# Analog_-_Low_Speed_SE.net
KiCad netlist of a schematic drawn in Altium Designer
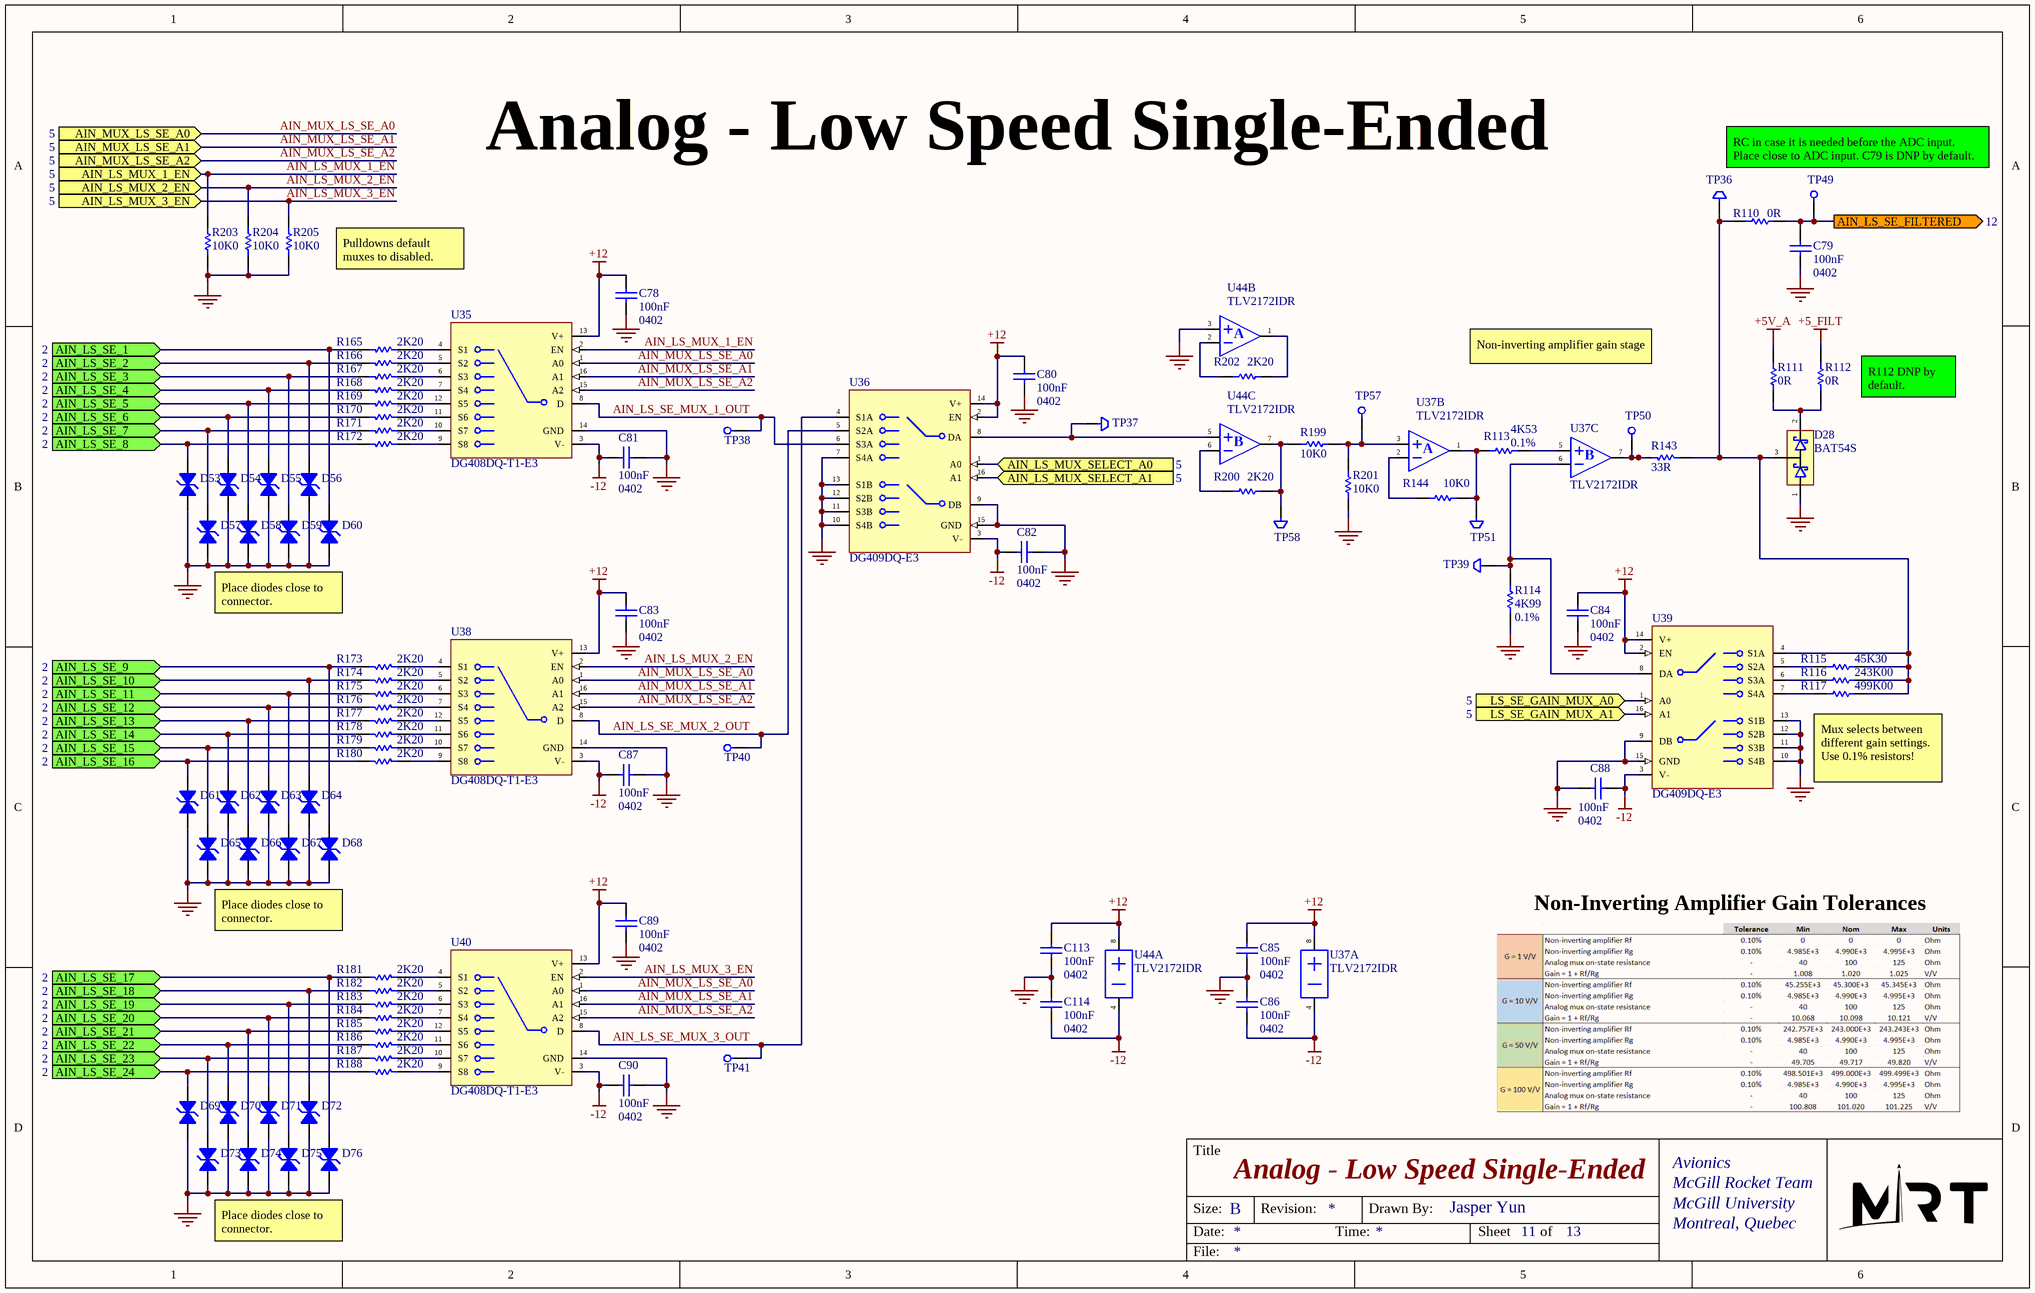
[diagram p0: Analog - Low Speed SE.SchDoc]

(export (version "E")
  (design (tool "Eeschema 10.0.6"))
  (components
    (comp (ref "C78")
      (value "100nF")
      (footprint "0402 CAP")
      (description "Capacitor")
      (fields (field (name "ALTIUM_VALUE") "0402") (field (name "PUBLISHER") "Altium Limited"))
      (libsource (lib "Miscellaneous Devices") (part "Cap"))
    )
    (comp (ref "C79")
      (value "100nF")
      (footprint "0402 CAP")
      (description "Capacitor")
      (fields (field (name "ALTIUM_VALUE") "0402") (field (name "PUBLISHER") "Altium Limited"))
      (libsource (lib "Miscellaneous Devices") (part "Cap"))
    )
    (comp (ref "C80")
      (value "100nF")
      (footprint "0402 CAP")
      (description "Capacitor")
      (fields (field (name "ALTIUM_VALUE") "0402") (field (name "PUBLISHER") "Altium Limited"))
      (libsource (lib "Miscellaneous Devices") (part "Cap"))
    )
    (comp (ref "C81")
      (value "100nF")
      (footprint "0402 CAP")
      (description "Capacitor")
      (fields (field (name "ALTIUM_VALUE") "0402") (field (name "PUBLISHER") "Altium Limited"))
      (libsource (lib "Miscellaneous Devices") (part "Cap"))
    )
    (comp (ref "C82")
      (value "100nF")
      (footprint "0402 CAP")
      (description "Capacitor")
      (fields (field (name "ALTIUM_VALUE") "0402") (field (name "PUBLISHER") "Altium Limited"))
      (libsource (lib "Miscellaneous Devices") (part "Cap"))
    )
    (comp (ref "C83")
      (value "100nF")
      (footprint "0402 CAP")
      (description "Capacitor")
      (fields (field (name "ALTIUM_VALUE") "0402") (field (name "PUBLISHER") "Altium Limited"))
      (libsource (lib "Miscellaneous Devices") (part "Cap"))
    )
    (comp (ref "C84")
      (value "100nF")
      (footprint "0402 CAP")
      (description "Capacitor")
      (fields (field (name "ALTIUM_VALUE") "0402") (field (name "PUBLISHER") "Altium Limited"))
      (libsource (lib "Miscellaneous Devices") (part "Cap"))
    )
    (comp (ref "C85")
      (value "100nF")
      (footprint "0402 CAP")
      (description "Capacitor")
      (fields (field (name "ALTIUM_VALUE") "0402") (field (name "PUBLISHER") "Altium Limited"))
      (libsource (lib "Miscellaneous Devices") (part "Cap"))
    )
    (comp (ref "C86")
      (value "100nF")
      (footprint "0402 CAP")
      (description "Capacitor")
      (fields (field (name "ALTIUM_VALUE") "0402") (field (name "PUBLISHER") "Altium Limited"))
      (libsource (lib "Miscellaneous Devices") (part "Cap"))
    )
    (comp (ref "C87")
      (value "100nF")
      (footprint "0402 CAP")
      (description "Capacitor")
      (fields (field (name "ALTIUM_VALUE") "0402") (field (name "PUBLISHER") "Altium Limited"))
      (libsource (lib "Miscellaneous Devices") (part "Cap"))
    )
    (comp (ref "C88")
      (value "100nF")
      (footprint "0402 CAP")
      (description "Capacitor")
      (fields (field (name "ALTIUM_VALUE") "0402") (field (name "PUBLISHER") "Altium Limited"))
      (libsource (lib "Miscellaneous Devices") (part "Cap"))
    )
    (comp (ref "C89")
      (value "100nF")
      (footprint "0402 CAP")
      (description "Capacitor")
      (fields (field (name "ALTIUM_VALUE") "0402") (field (name "PUBLISHER") "Altium Limited"))
      (libsource (lib "Miscellaneous Devices") (part "Cap"))
    )
    (comp (ref "C90")
      (value "100nF")
      (footprint "0402 CAP")
      (description "Capacitor")
      (fields (field (name "ALTIUM_VALUE") "0402") (field (name "PUBLISHER") "Altium Limited"))
      (libsource (lib "Miscellaneous Devices") (part "Cap"))
    )
    (comp (ref "C113")
      (value "100nF")
      (footprint "0402 CAP")
      (description "Capacitor")
      (fields (field (name "ALTIUM_VALUE") "0402") (field (name "PUBLISHER") "Altium Limited"))
      (libsource (lib "Miscellaneous Devices") (part "Cap"))
    )
    (comp (ref "C114")
      (value "100nF")
      (footprint "0402 CAP")
      (description "Capacitor")
      (fields (field (name "ALTIUM_VALUE") "0402") (field (name "PUBLISHER") "Altium Limited"))
      (libsource (lib "Miscellaneous Devices") (part "Cap"))
    )
    (comp (ref "D28")
      (value "BAT54S")
      (footprint "SOT23-3")
      (description "Rectifier Diode Small Signal Schottky 40V 0.3A 5ns 3-Pin SOT-23 T/R")
      (fields
        (field (name "MANUFACTURER") "STMicroelectronics")
        (field (name "MANUFACTURER PART NUMBER") "BAT54SFILM")
      )
      (libsource (lib "MRT SCH Library") (part "Schottky Diode Array BAT54S"))
    )
    (comp (ref "D53")
      (value "D12V0L1B2LP-7B")
      (footprint "DFN1006-2")
      (description "Bidirectional Zener diode")
      (libsource (lib "MRT SCH Library") (part "Diode Zener Bidirectional"))
    )
    (comp (ref "D54")
      (value "D12V0L1B2LP-7B")
      (footprint "DFN1006-2")
      (description "Bidirectional Zener diode")
      (libsource (lib "MRT SCH Library") (part "Diode Zener Bidirectional"))
    )
    (comp (ref "D55")
      (value "D12V0L1B2LP-7B")
      (footprint "DFN1006-2")
      (description "Bidirectional Zener diode")
      (libsource (lib "MRT SCH Library") (part "Diode Zener Bidirectional"))
    )
    (comp (ref "D56")
      (value "D12V0L1B2LP-7B")
      (footprint "DFN1006-2")
      (description "Bidirectional Zener diode")
      (libsource (lib "MRT SCH Library") (part "Diode Zener Bidirectional"))
    )
    (comp (ref "D57")
      (value "D12V0L1B2LP-7B")
      (footprint "DFN1006-2")
      (description "Bidirectional Zener diode")
      (libsource (lib "MRT SCH Library") (part "Diode Zener Bidirectional"))
    )
    (comp (ref "D58")
      (value "D12V0L1B2LP-7B")
      (footprint "DFN1006-2")
      (description "Bidirectional Zener diode")
      (libsource (lib "MRT SCH Library") (part "Diode Zener Bidirectional"))
    )
    (comp (ref "D59")
      (value "D12V0L1B2LP-7B")
      (footprint "DFN1006-2")
      (description "Bidirectional Zener diode")
      (libsource (lib "MRT SCH Library") (part "Diode Zener Bidirectional"))
    )
    (comp (ref "D60")
      (value "D12V0L1B2LP-7B")
      (footprint "DFN1006-2")
      (description "Bidirectional Zener diode")
      (libsource (lib "MRT SCH Library") (part "Diode Zener Bidirectional"))
    )
    (comp (ref "D61")
      (value "D12V0L1B2LP-7B")
      (footprint "DFN1006-2")
      (description "Bidirectional Zener diode")
      (libsource (lib "MRT SCH Library") (part "Diode Zener Bidirectional"))
    )
    (comp (ref "D62")
      (value "D12V0L1B2LP-7B")
      (footprint "DFN1006-2")
      (description "Bidirectional Zener diode")
      (libsource (lib "MRT SCH Library") (part "Diode Zener Bidirectional"))
    )
    (comp (ref "D63")
      (value "D12V0L1B2LP-7B")
      (footprint "DFN1006-2")
      (description "Bidirectional Zener diode")
      (libsource (lib "MRT SCH Library") (part "Diode Zener Bidirectional"))
    )
    (comp (ref "D64")
      (value "D12V0L1B2LP-7B")
      (footprint "DFN1006-2")
      (description "Bidirectional Zener diode")
      (libsource (lib "MRT SCH Library") (part "Diode Zener Bidirectional"))
    )
    (comp (ref "D65")
      (value "D12V0L1B2LP-7B")
      (footprint "DFN1006-2")
      (description "Bidirectional Zener diode")
      (libsource (lib "MRT SCH Library") (part "Diode Zener Bidirectional"))
    )
    (comp (ref "D66")
      (value "D12V0L1B2LP-7B")
      (footprint "DFN1006-2")
      (description "Bidirectional Zener diode")
      (libsource (lib "MRT SCH Library") (part "Diode Zener Bidirectional"))
    )
    (comp (ref "D67")
      (value "D12V0L1B2LP-7B")
      (footprint "DFN1006-2")
      (description "Bidirectional Zener diode")
      (libsource (lib "MRT SCH Library") (part "Diode Zener Bidirectional"))
    )
    (comp (ref "D68")
      (value "D12V0L1B2LP-7B")
      (footprint "DFN1006-2")
      (description "Bidirectional Zener diode")
      (libsource (lib "MRT SCH Library") (part "Diode Zener Bidirectional"))
    )
    (comp (ref "D69")
      (value "D12V0L1B2LP-7B")
      (footprint "DFN1006-2")
      (description "Bidirectional Zener diode")
      (libsource (lib "MRT SCH Library") (part "Diode Zener Bidirectional"))
    )
    (comp (ref "D70")
      (value "D12V0L1B2LP-7B")
      (footprint "DFN1006-2")
      (description "Bidirectional Zener diode")
      (libsource (lib "MRT SCH Library") (part "Diode Zener Bidirectional"))
    )
    (comp (ref "D71")
      (value "D12V0L1B2LP-7B")
      (footprint "DFN1006-2")
      (description "Bidirectional Zener diode")
      (libsource (lib "MRT SCH Library") (part "Diode Zener Bidirectional"))
    )
    (comp (ref "D72")
      (value "D12V0L1B2LP-7B")
      (footprint "DFN1006-2")
      (description "Bidirectional Zener diode")
      (libsource (lib "MRT SCH Library") (part "Diode Zener Bidirectional"))
    )
    (comp (ref "D73")
      (value "D12V0L1B2LP-7B")
      (footprint "DFN1006-2")
      (description "Bidirectional Zener diode")
      (libsource (lib "MRT SCH Library") (part "Diode Zener Bidirectional"))
    )
    (comp (ref "D74")
      (value "D12V0L1B2LP-7B")
      (footprint "DFN1006-2")
      (description "Bidirectional Zener diode")
      (libsource (lib "MRT SCH Library") (part "Diode Zener Bidirectional"))
    )
    (comp (ref "D75")
      (value "D12V0L1B2LP-7B")
      (footprint "DFN1006-2")
      (description "Bidirectional Zener diode")
      (libsource (lib "MRT SCH Library") (part "Diode Zener Bidirectional"))
    )
    (comp (ref "D76")
      (value "D12V0L1B2LP-7B")
      (footprint "DFN1006-2")
      (description "Bidirectional Zener diode")
      (libsource (lib "MRT SCH Library") (part "Diode Zener Bidirectional"))
    )
    (comp (ref "R110")
      (value "0R")
      (footprint "0402 RES")
      (description "Resistor")
      (fields (field (name "PUBLISHER") "Altium Limited"))
      (libsource (lib "Miscellaneous Devices") (part "Res1"))
    )
    (comp (ref "R111")
      (value "0R")
      (footprint "0402 RES")
      (description "Resistor")
      (fields (field (name "PUBLISHER") "Altium Limited"))
      (libsource (lib "Miscellaneous Devices") (part "Res1"))
    )
    (comp (ref "R112")
      (value "0R")
      (footprint "0402 RES")
      (description "Resistor")
      (fields (field (name "PUBLISHER") "Altium Limited"))
      (libsource (lib "Miscellaneous Devices") (part "Res1"))
    )
    (comp (ref "R113")
      (value "4K53")
      (footprint "0402 RES")
      (description "Resistor")
      (fields (field (name "ALTIUM_VALUE") "0.1%") (field (name "PUBLISHER") "Altium Limited"))
      (libsource (lib "Miscellaneous Devices") (part "Res1"))
    )
    (comp (ref "R114")
      (value "4K99")
      (footprint "0402 RES")
      (description "Resistor")
      (fields (field (name "ALTIUM_VALUE") "0.1%") (field (name "PUBLISHER") "Altium Limited"))
      (libsource (lib "Miscellaneous Devices") (part "Res1"))
    )
    (comp (ref "R115")
      (value "45K30")
      (footprint "0402 RES")
      (description "Resistor")
      (fields (field (name "PUBLISHER") "Altium Limited"))
      (libsource (lib "Miscellaneous Devices") (part "Res1"))
    )
    (comp (ref "R116")
      (value "243K00")
      (footprint "0402 RES")
      (description "Resistor")
      (fields (field (name "PUBLISHER") "Altium Limited"))
      (libsource (lib "Miscellaneous Devices") (part "Res1"))
    )
    (comp (ref "R117")
      (value "499K00")
      (footprint "0402 RES")
      (description "Resistor")
      (fields (field (name "PUBLISHER") "Altium Limited"))
      (libsource (lib "Miscellaneous Devices") (part "Res1"))
    )
    (comp (ref "R143")
      (value "33R")
      (footprint "0402 RES")
      (description "Resistor")
      (fields (field (name "PUBLISHER") "Altium Limited"))
      (libsource (lib "Miscellaneous Devices") (part "Res1"))
    )
    (comp (ref "R144")
      (value "10K0")
      (footprint "0402 RES")
      (description "Resistor")
      (fields (field (name "PUBLISHER") "Altium Limited"))
      (libsource (lib "Miscellaneous Devices") (part "Res1"))
    )
    (comp (ref "R165")
      (value "2K20")
      (footprint "0402 RES")
      (description "Resistor")
      (fields (field (name "PUBLISHER") "Altium Limited"))
      (libsource (lib "Miscellaneous Devices") (part "Res1"))
    )
    (comp (ref "R166")
      (value "2K20")
      (footprint "0402 RES")
      (description "Resistor")
      (fields (field (name "PUBLISHER") "Altium Limited"))
      (libsource (lib "Miscellaneous Devices") (part "Res1"))
    )
    (comp (ref "R167")
      (value "2K20")
      (footprint "0402 RES")
      (description "Resistor")
      (fields (field (name "PUBLISHER") "Altium Limited"))
      (libsource (lib "Miscellaneous Devices") (part "Res1"))
    )
    (comp (ref "R168")
      (value "2K20")
      (footprint "0402 RES")
      (description "Resistor")
      (fields (field (name "PUBLISHER") "Altium Limited"))
      (libsource (lib "Miscellaneous Devices") (part "Res1"))
    )
    (comp (ref "R169")
      (value "2K20")
      (footprint "0402 RES")
      (description "Resistor")
      (fields (field (name "PUBLISHER") "Altium Limited"))
      (libsource (lib "Miscellaneous Devices") (part "Res1"))
    )
    (comp (ref "R170")
      (value "2K20")
      (footprint "0402 RES")
      (description "Resistor")
      (fields (field (name "PUBLISHER") "Altium Limited"))
      (libsource (lib "Miscellaneous Devices") (part "Res1"))
    )
    (comp (ref "R171")
      (value "2K20")
      (footprint "0402 RES")
      (description "Resistor")
      (fields (field (name "PUBLISHER") "Altium Limited"))
      (libsource (lib "Miscellaneous Devices") (part "Res1"))
    )
    (comp (ref "R172")
      (value "2K20")
      (footprint "0402 RES")
      (description "Resistor")
      (fields (field (name "PUBLISHER") "Altium Limited"))
      (libsource (lib "Miscellaneous Devices") (part "Res1"))
    )
    (comp (ref "R173")
      (value "2K20")
      (footprint "0402 RES")
      (description "Resistor")
      (fields (field (name "PUBLISHER") "Altium Limited"))
      (libsource (lib "Miscellaneous Devices") (part "Res1"))
    )
    (comp (ref "R174")
      (value "2K20")
      (footprint "0402 RES")
      (description "Resistor")
      (fields (field (name "PUBLISHER") "Altium Limited"))
      (libsource (lib "Miscellaneous Devices") (part "Res1"))
    )
    (comp (ref "R175")
      (value "2K20")
      (footprint "0402 RES")
      (description "Resistor")
      (fields (field (name "PUBLISHER") "Altium Limited"))
      (libsource (lib "Miscellaneous Devices") (part "Res1"))
    )
    (comp (ref "R176")
      (value "2K20")
      (footprint "0402 RES")
      (description "Resistor")
      (fields (field (name "PUBLISHER") "Altium Limited"))
      (libsource (lib "Miscellaneous Devices") (part "Res1"))
    )
    (comp (ref "R177")
      (value "2K20")
      (footprint "0402 RES")
      (description "Resistor")
      (fields (field (name "PUBLISHER") "Altium Limited"))
      (libsource (lib "Miscellaneous Devices") (part "Res1"))
    )
    (comp (ref "R178")
      (value "2K20")
      (footprint "0402 RES")
      (description "Resistor")
      (fields (field (name "PUBLISHER") "Altium Limited"))
      (libsource (lib "Miscellaneous Devices") (part "Res1"))
    )
    (comp (ref "R179")
      (value "2K20")
      (footprint "0402 RES")
      (description "Resistor")
      (fields (field (name "PUBLISHER") "Altium Limited"))
      (libsource (lib "Miscellaneous Devices") (part "Res1"))
    )
    (comp (ref "R180")
      (value "2K20")
      (footprint "0402 RES")
      (description "Resistor")
      (fields (field (name "PUBLISHER") "Altium Limited"))
      (libsource (lib "Miscellaneous Devices") (part "Res1"))
    )
    (comp (ref "R181")
      (value "2K20")
      (footprint "0402 RES")
      (description "Resistor")
      (fields (field (name "PUBLISHER") "Altium Limited"))
      (libsource (lib "Miscellaneous Devices") (part "Res1"))
    )
    (comp (ref "R182")
      (value "2K20")
      (footprint "0402 RES")
      (description "Resistor")
      (fields (field (name "PUBLISHER") "Altium Limited"))
      (libsource (lib "Miscellaneous Devices") (part "Res1"))
    )
    (comp (ref "R183")
      (value "2K20")
      (footprint "0402 RES")
      (description "Resistor")
      (fields (field (name "PUBLISHER") "Altium Limited"))
      (libsource (lib "Miscellaneous Devices") (part "Res1"))
    )
    (comp (ref "R184")
      (value "2K20")
      (footprint "0402 RES")
      (description "Resistor")
      (fields (field (name "PUBLISHER") "Altium Limited"))
      (libsource (lib "Miscellaneous Devices") (part "Res1"))
    )
    (comp (ref "R185")
      (value "2K20")
      (footprint "0402 RES")
      (description "Resistor")
      (fields (field (name "PUBLISHER") "Altium Limited"))
      (libsource (lib "Miscellaneous Devices") (part "Res1"))
    )
    (comp (ref "R186")
      (value "2K20")
      (footprint "0402 RES")
      (description "Resistor")
      (fields (field (name "PUBLISHER") "Altium Limited"))
      (libsource (lib "Miscellaneous Devices") (part "Res1"))
    )
    (comp (ref "R187")
      (value "2K20")
      (footprint "0402 RES")
      (description "Resistor")
      (fields (field (name "PUBLISHER") "Altium Limited"))
      (libsource (lib "Miscellaneous Devices") (part "Res1"))
    )
    (comp (ref "R188")
      (value "2K20")
      (footprint "0402 RES")
      (description "Resistor")
      (fields (field (name "PUBLISHER") "Altium Limited"))
      (libsource (lib "Miscellaneous Devices") (part "Res1"))
    )
    (comp (ref "R199")
      (value "10K0")
      (footprint "0402 RES")
      (description "Resistor")
      (fields (field (name "PUBLISHER") "Altium Limited"))
      (libsource (lib "Miscellaneous Devices") (part "Res1"))
    )
    (comp (ref "R200")
      (value "2K20")
      (footprint "0402 RES")
      (description "Resistor")
      (fields (field (name "PUBLISHER") "Altium Limited"))
      (libsource (lib "Miscellaneous Devices") (part "Res1"))
    )
    (comp (ref "R201")
      (value "10K0")
      (footprint "0402 RES")
      (description "Resistor")
      (fields (field (name "PUBLISHER") "Altium Limited"))
      (libsource (lib "Miscellaneous Devices") (part "Res1"))
    )
    (comp (ref "R202")
      (value "2K20")
      (footprint "0402 RES")
      (description "Resistor")
      (fields (field (name "PUBLISHER") "Altium Limited"))
      (libsource (lib "Miscellaneous Devices") (part "Res1"))
    )
    (comp (ref "R203")
      (value "10K0")
      (footprint "0402 RES")
      (description "Resistor")
      (fields (field (name "PUBLISHER") "Altium Limited"))
      (libsource (lib "Miscellaneous Devices") (part "Res1"))
    )
    (comp (ref "R204")
      (value "10K0")
      (footprint "0402 RES")
      (description "Resistor")
      (fields (field (name "PUBLISHER") "Altium Limited"))
      (libsource (lib "Miscellaneous Devices") (part "Res1"))
    )
    (comp (ref "R205")
      (value "10K0")
      (footprint "0402 RES")
      (description "Resistor")
      (fields (field (name "PUBLISHER") "Altium Limited"))
      (libsource (lib "Miscellaneous Devices") (part "Res1"))
    )
    (comp (ref "TP36")
      (value "Test Point - Keystone 5015")
      (footprint "Test Point Keystone 5015")
      (description "Keystone 5015 Test point")
      (libsource (lib "MRT SCH Library") (part "Test Point - Keystone 5015"))
    )
    (comp (ref "TP37")
      (value "Test Point - Keystone 5015")
      (footprint "Test Point Keystone 5015")
      (description "Keystone 5015 Test point")
      (libsource (lib "MRT SCH Library") (part "Test Point - Keystone 5015"))
    )
    (comp (ref "TP38")
      (value "Test Point - SMD Pad")
      (footprint "TEST POINT SMD PAD")
      (description "SMD Pad test point")
      (libsource (lib "MRT SCH Library") (part "Test Point - SMD Pad"))
    )
    (comp (ref "TP39")
      (value "Test Point - Keystone 5015")
      (footprint "Test Point Keystone 5015")
      (description "Keystone 5015 Test point")
      (libsource (lib "MRT SCH Library") (part "Test Point - Keystone 5015"))
    )
    (comp (ref "TP40")
      (value "Test Point - SMD Pad")
      (footprint "TEST POINT SMD PAD")
      (description "SMD Pad test point")
      (libsource (lib "MRT SCH Library") (part "Test Point - SMD Pad"))
    )
    (comp (ref "TP41")
      (value "Test Point - SMD Pad")
      (footprint "TEST POINT SMD PAD")
      (description "SMD Pad test point")
      (libsource (lib "MRT SCH Library") (part "Test Point - SMD Pad"))
    )
    (comp (ref "TP49")
      (value "Test Point - SMD Pad")
      (footprint "TEST POINT SMD PAD")
      (description "SMD Pad test point")
      (libsource (lib "MRT SCH Library") (part "Test Point - SMD Pad"))
    )
    (comp (ref "TP50")
      (value "Test Point - SMD Pad")
      (footprint "TEST POINT SMD PAD")
      (description "SMD Pad test point")
      (libsource (lib "MRT SCH Library") (part "Test Point - SMD Pad"))
    )
    (comp (ref "TP51")
      (value "Test Point - Keystone 5015")
      (footprint "Test Point Keystone 5015")
      (description "Keystone 5015 Test point")
      (libsource (lib "MRT SCH Library") (part "Test Point - Keystone 5015"))
    )
    (comp (ref "TP57")
      (value "Test Point - SMD Pad")
      (footprint "TEST POINT SMD PAD")
      (description "SMD Pad test point")
      (libsource (lib "MRT SCH Library") (part "Test Point - SMD Pad"))
    )
    (comp (ref "TP58")
      (value "Test Point - Keystone 5015")
      (footprint "Test Point Keystone 5015")
      (description "Keystone 5015 Test point")
      (libsource (lib "MRT SCH Library") (part "Test Point - Keystone 5015"))
    )
    (comp (ref "U35")
      (value "DG408DQ-T1-E3")
      (footprint "TSSOP-16")
      (description "DG408DQ-T1-E3; Multiplexer Single 8: 1; 15 V; 18 V; 24 V; 28 V; 16-Pin TSSOP")
      (fields (field (name "MANUFACTURER") "Vishay Siliconix"))
      (libsource (lib "MRT SCH Library") (part "Analog Mux DG408DQ-T1-E3"))
    )
    (comp (ref "U36")
      (value "DG409DQ-E3")
      (footprint "TSSOP-16")
      (description "DG409 Series 20 V 8-Ch/Dual 4-Ch High-Performance CMOS Analog Multiplexer")
      (fields (field (name "MANUFACTURER") "Vishay Siliconix"))
      (libsource (lib "") (part "Analog Mux DG409DQ-E3_1"))
    )
    (comp (ref "U37")
      (value "TLV2172IDR")
      (footprint "SOIC-8")
      (fields
        (field (name "MANUFACTURER") "Texas Instruments")
        (field (name "MANUFACTURER PART NUMBER") "RC4580IDR")
      )
      (libsource (lib "MRT SCH Library") (part "OP AMP RC4580"))
    )
    (comp (ref "U38")
      (value "DG408DQ-T1-E3")
      (footprint "TSSOP-16")
      (description "DG408DQ-T1-E3; Multiplexer Single 8: 1; 15 V; 18 V; 24 V; 28 V; 16-Pin TSSOP")
      (fields (field (name "MANUFACTURER") "Vishay Siliconix"))
      (libsource (lib "MRT SCH Library") (part "Analog Mux DG408DQ-T1-E3"))
    )
    (comp (ref "U39")
      (value "DG409DQ-E3")
      (footprint "TSSOP-16")
      (description "DG409 Series 20 V 8-Ch/Dual 4-Ch High-Performance CMOS Analog Multiplexer")
      (fields (field (name "MANUFACTURER") "Vishay Siliconix"))
      (libsource (lib "MRT SCH Library") (part "Analog Mux DG409DQ-E3"))
    )
    (comp (ref "U40")
      (value "DG408DQ-T1-E3")
      (footprint "TSSOP-16")
      (description "DG408DQ-T1-E3; Multiplexer Single 8: 1; 15 V; 18 V; 24 V; 28 V; 16-Pin TSSOP")
      (fields (field (name "MANUFACTURER") "Vishay Siliconix"))
      (libsource (lib "MRT SCH Library") (part "Analog Mux DG408DQ-T1-E3"))
    )
    (comp (ref "U44")
      (value "TLV2172IDR")
      (footprint "SOIC-8")
      (fields
        (field (name "MANUFACTURER") "Texas Instruments")
        (field (name "MANUFACTURER PART NUMBER") "RC4580IDR")
      )
      (libsource (lib "MRT SCH Library") (part "OP AMP RC4580"))
    )
  )
  (nets
    (net (code "1") (name "+5V_A") (class "Default")
      (node (ref "R111") (pin "1") (pinfunction "1_1") (pintype "passive"))
    )
    (net (code "2") (name "+5_FILT") (class "Default")
      (node (ref "R112") (pin "1") (pinfunction "1_1") (pintype "passive"))
    )
    (net (code "3") (name "+12") (class "Default")
      (node (ref "C113") (pin "2") (pinfunction "2_2") (pintype "passive"))
      (node (ref "C78") (pin "2") (pinfunction "2_2") (pintype "passive"))
      (node (ref "C80") (pin "2") (pinfunction "2_2") (pintype "passive"))
      (node (ref "C83") (pin "2") (pinfunction "2_2") (pintype "passive"))
      (node (ref "C84") (pin "2") (pinfunction "2_2") (pintype "passive"))
      (node (ref "C85") (pin "2") (pinfunction "2_2") (pintype "passive"))
      (node (ref "C89") (pin "2") (pinfunction "2_2") (pintype "passive"))
      (node (ref "U35") (pin "13") (pinfunction "V+_13") (pintype "passive"))
      (node (ref "U36") (pin "14") (pinfunction "V+_14") (pintype "passive"))
      (node (ref "U36") (pin "2") (pinfunction "EN_2") (pintype "input"))
      (node (ref "U37") (pin "8") (pinfunction "VCC+_8") (pintype "passive"))
      (node (ref "U38") (pin "13") (pinfunction "V+_13") (pintype "passive"))
      (node (ref "U39") (pin "14") (pinfunction "V+_14") (pintype "passive"))
      (node (ref "U39") (pin "2") (pinfunction "EN_2") (pintype "input"))
      (node (ref "U40") (pin "13") (pinfunction "V+_13") (pintype "passive"))
      (node (ref "U44") (pin "8") (pinfunction "VCC+_8") (pintype "passive"))
    )
    (net (code "4") (name "-12") (class "Default")
      (node (ref "C114") (pin "1") (pinfunction "1_1") (pintype "passive"))
      (node (ref "C81") (pin "2") (pinfunction "2_2") (pintype "passive"))
      (node (ref "C82") (pin "2") (pinfunction "2_2") (pintype "passive"))
      (node (ref "C86") (pin "1") (pinfunction "1_1") (pintype "passive"))
      (node (ref "C87") (pin "2") (pinfunction "2_2") (pintype "passive"))
      (node (ref "C88") (pin "2") (pinfunction "2_2") (pintype "passive"))
      (node (ref "C90") (pin "2") (pinfunction "2_2") (pintype "passive"))
      (node (ref "U35") (pin "3") (pinfunction "V-_3") (pintype "passive"))
      (node (ref "U36") (pin "3") (pinfunction "V-_3") (pintype "passive"))
      (node (ref "U37") (pin "4") (pinfunction "VCC-_4") (pintype "passive"))
      (node (ref "U38") (pin "3") (pinfunction "V-_3") (pintype "passive"))
      (node (ref "U39") (pin "3") (pinfunction "V-_3") (pintype "passive"))
      (node (ref "U40") (pin "3") (pinfunction "V-_3") (pintype "passive"))
      (node (ref "U44") (pin "4") (pinfunction "VCC-_4") (pintype "passive"))
    )
    (net (code "5") (name "/AIN_LS_MUX_1_EN") (class "Default")
      (node (ref "R203") (pin "1") (pinfunction "1_1") (pintype "passive"))
      (node (ref "U35") (pin "2") (pinfunction "EN_2") (pintype "input"))
    )
    (net (code "6") (name "/AIN_LS_MUX_2_EN") (class "Default")
      (node (ref "R204") (pin "1") (pinfunction "1_1") (pintype "passive"))
      (node (ref "U38") (pin "2") (pinfunction "EN_2") (pintype "input"))
    )
    (net (code "7") (name "/AIN_LS_MUX_3_EN") (class "Default")
      (node (ref "R205") (pin "1") (pinfunction "1_1") (pintype "passive"))
      (node (ref "U40") (pin "2") (pinfunction "EN_2") (pintype "input"))
    )
    (net (code "8") (name "/AIN_LS_MUX_SELECT_A0") (class "Default")
      (node (ref "U36") (pin "1") (pinfunction "A0_1") (pintype "input"))
    )
    (net (code "9") (name "/AIN_LS_MUX_SELECT_A1") (class "Default")
      (node (ref "U36") (pin "16") (pinfunction "A1_16") (pintype "input"))
    )
    (net (code "10") (name "/AIN_LS_SE_1") (class "Default")
      (node (ref "D60") (pin "2") (pinfunction "2_2") (pintype "passive"))
      (node (ref "R165") (pin "1") (pinfunction "1_1") (pintype "passive"))
    )
    (net (code "11") (name "/AIN_LS_SE_2") (class "Default")
      (node (ref "D56") (pin "2") (pinfunction "2_2") (pintype "passive"))
      (node (ref "R166") (pin "1") (pinfunction "1_1") (pintype "passive"))
    )
    (net (code "12") (name "/AIN_LS_SE_3") (class "Default")
      (node (ref "D59") (pin "2") (pinfunction "2_2") (pintype "passive"))
      (node (ref "R167") (pin "1") (pinfunction "1_1") (pintype "passive"))
    )
    (net (code "13") (name "/AIN_LS_SE_4") (class "Default")
      (node (ref "D55") (pin "2") (pinfunction "2_2") (pintype "passive"))
      (node (ref "R168") (pin "1") (pinfunction "1_1") (pintype "passive"))
    )
    (net (code "14") (name "/AIN_LS_SE_5") (class "Default")
      (node (ref "D58") (pin "2") (pinfunction "2_2") (pintype "passive"))
      (node (ref "R169") (pin "1") (pinfunction "1_1") (pintype "passive"))
    )
    (net (code "15") (name "/AIN_LS_SE_6") (class "Default")
      (node (ref "D54") (pin "2") (pinfunction "2_2") (pintype "passive"))
      (node (ref "R170") (pin "1") (pinfunction "1_1") (pintype "passive"))
    )
    (net (code "16") (name "/AIN_LS_SE_7") (class "Default")
      (node (ref "D57") (pin "2") (pinfunction "2_2") (pintype "passive"))
      (node (ref "R171") (pin "1") (pinfunction "1_1") (pintype "passive"))
    )
    (net (code "17") (name "/AIN_LS_SE_8") (class "Default")
      (node (ref "D53") (pin "2") (pinfunction "2_2") (pintype "passive"))
      (node (ref "R172") (pin "1") (pinfunction "1_1") (pintype "passive"))
    )
    (net (code "18") (name "/AIN_LS_SE_9") (class "Default")
      (node (ref "D68") (pin "2") (pinfunction "2_2") (pintype "passive"))
      (node (ref "R173") (pin "1") (pinfunction "1_1") (pintype "passive"))
    )
    (net (code "19") (name "/AIN_LS_SE_10") (class "Default")
      (node (ref "D64") (pin "2") (pinfunction "2_2") (pintype "passive"))
      (node (ref "R174") (pin "1") (pinfunction "1_1") (pintype "passive"))
    )
    (net (code "20") (name "/AIN_LS_SE_11") (class "Default")
      (node (ref "D67") (pin "2") (pinfunction "2_2") (pintype "passive"))
      (node (ref "R175") (pin "1") (pinfunction "1_1") (pintype "passive"))
    )
    (net (code "21") (name "/AIN_LS_SE_12") (class "Default")
      (node (ref "D63") (pin "2") (pinfunction "2_2") (pintype "passive"))
      (node (ref "R176") (pin "1") (pinfunction "1_1") (pintype "passive"))
    )
    (net (code "22") (name "/AIN_LS_SE_13") (class "Default")
      (node (ref "D66") (pin "2") (pinfunction "2_2") (pintype "passive"))
      (node (ref "R177") (pin "1") (pinfunction "1_1") (pintype "passive"))
    )
    (net (code "23") (name "/AIN_LS_SE_14") (class "Default")
      (node (ref "D62") (pin "2") (pinfunction "2_2") (pintype "passive"))
      (node (ref "R178") (pin "1") (pinfunction "1_1") (pintype "passive"))
    )
    (net (code "24") (name "/AIN_LS_SE_15") (class "Default")
      (node (ref "D65") (pin "2") (pinfunction "2_2") (pintype "passive"))
      (node (ref "R179") (pin "1") (pinfunction "1_1") (pintype "passive"))
    )
    (net (code "25") (name "/AIN_LS_SE_16") (class "Default")
      (node (ref "D61") (pin "2") (pinfunction "2_2") (pintype "passive"))
      (node (ref "R180") (pin "1") (pinfunction "1_1") (pintype "passive"))
    )
    (net (code "26") (name "/AIN_LS_SE_17") (class "Default")
      (node (ref "D76") (pin "2") (pinfunction "2_2") (pintype "passive"))
      (node (ref "R181") (pin "1") (pinfunction "1_1") (pintype "passive"))
    )
    (net (code "27") (name "/AIN_LS_SE_18") (class "Default")
      (node (ref "D72") (pin "2") (pinfunction "2_2") (pintype "passive"))
      (node (ref "R182") (pin "1") (pinfunction "1_1") (pintype "passive"))
    )
    (net (code "28") (name "/AIN_LS_SE_19") (class "Default")
      (node (ref "D75") (pin "2") (pinfunction "2_2") (pintype "passive"))
      (node (ref "R183") (pin "1") (pinfunction "1_1") (pintype "passive"))
    )
    (net (code "29") (name "/AIN_LS_SE_20") (class "Default")
      (node (ref "D71") (pin "2") (pinfunction "2_2") (pintype "passive"))
      (node (ref "R184") (pin "1") (pinfunction "1_1") (pintype "passive"))
    )
    (net (code "30") (name "/AIN_LS_SE_21") (class "Default")
      (node (ref "D74") (pin "2") (pinfunction "2_2") (pintype "passive"))
      (node (ref "R185") (pin "1") (pinfunction "1_1") (pintype "passive"))
    )
    (net (code "31") (name "/AIN_LS_SE_22") (class "Default")
      (node (ref "D70") (pin "2") (pinfunction "2_2") (pintype "passive"))
      (node (ref "R186") (pin "1") (pinfunction "1_1") (pintype "passive"))
    )
    (net (code "32") (name "/AIN_LS_SE_23") (class "Default")
      (node (ref "D73") (pin "2") (pinfunction "2_2") (pintype "passive"))
      (node (ref "R187") (pin "1") (pinfunction "1_1") (pintype "passive"))
    )
    (net (code "33") (name "/AIN_LS_SE_24") (class "Default")
      (node (ref "D69") (pin "2") (pinfunction "2_2") (pintype "passive"))
      (node (ref "R188") (pin "1") (pinfunction "1_1") (pintype "passive"))
    )
    (net (code "34") (name "/AIN_LS_SE_FILTERED") (class "Default")
      (node (ref "C79") (pin "2") (pinfunction "2_2") (pintype "passive"))
      (node (ref "R110") (pin "1") (pinfunction "1_1") (pintype "passive"))
      (node (ref "TP49") (pin "1") (pinfunction "1_1") (pintype "passive"))
    )
    (net (code "35") (name "/AIN_LS_SE_MUX_1_OUT") (class "Default")
      (node (ref "TP38") (pin "1") (pinfunction "1_1") (pintype "passive"))
      (node (ref "U35") (pin "8") (pinfunction "D_8") (pintype "passive"))
      (node (ref "U36") (pin "6") (pinfunction "S3A_6") (pintype "passive"))
    )
    (net (code "36") (name "/AIN_LS_SE_MUX_2_OUT") (class "Default")
      (node (ref "TP40") (pin "1") (pinfunction "1_1") (pintype "passive"))
      (node (ref "U36") (pin "5") (pinfunction "S2A_5") (pintype "passive"))
      (node (ref "U38") (pin "8") (pinfunction "D_8") (pintype "passive"))
    )
    (net (code "37") (name "/AIN_LS_SE_MUX_3_OUT") (class "Default")
      (node (ref "TP41") (pin "1") (pinfunction "1_1") (pintype "passive"))
      (node (ref "U36") (pin "4") (pinfunction "S1A_4") (pintype "passive"))
      (node (ref "U40") (pin "8") (pinfunction "D_8") (pintype "passive"))
    )
    (net (code "38") (name "/AIN_MUX_LS_SE_A0") (class "Default")
      (node (ref "U35") (pin "1") (pinfunction "A0_1") (pintype "input"))
      (node (ref "U38") (pin "1") (pinfunction "A0_1") (pintype "input"))
      (node (ref "U40") (pin "1") (pinfunction "A0_1") (pintype "input"))
    )
    (net (code "39") (name "/AIN_MUX_LS_SE_A1") (class "Default")
      (node (ref "U35") (pin "16") (pinfunction "A1_16") (pintype "input"))
      (node (ref "U38") (pin "16") (pinfunction "A1_16") (pintype "input"))
      (node (ref "U40") (pin "16") (pinfunction "A1_16") (pintype "input"))
    )
    (net (code "40") (name "/AIN_MUX_LS_SE_A2") (class "Default")
      (node (ref "U35") (pin "15") (pinfunction "A2_15") (pintype "input"))
      (node (ref "U38") (pin "15") (pinfunction "A2_15") (pintype "input"))
      (node (ref "U40") (pin "15") (pinfunction "A2_15") (pintype "input"))
    )
    (net (code "41") (name "/LS_SE_GAIN_MUX_A0") (class "Default")
      (node (ref "U39") (pin "1") (pinfunction "A0_1") (pintype "input"))
    )
    (net (code "42") (name "/LS_SE_GAIN_MUX_A1") (class "Default")
      (node (ref "U39") (pin "16") (pinfunction "A1_16") (pintype "input"))
    )
    (net (code "43") (name "GND") (class "Default")
      (node (ref "C113") (pin "1") (pinfunction "1_1") (pintype "passive"))
      (node (ref "C114") (pin "2") (pinfunction "2_2") (pintype "passive"))
      (node (ref "C78") (pin "1") (pinfunction "1_1") (pintype "passive"))
      (node (ref "C79") (pin "1") (pinfunction "1_1") (pintype "passive"))
      (node (ref "C80") (pin "1") (pinfunction "1_1") (pintype "passive"))
      (node (ref "C81") (pin "1") (pinfunction "1_1") (pintype "passive"))
      (node (ref "C82") (pin "1") (pinfunction "1_1") (pintype "passive"))
      (node (ref "C83") (pin "1") (pinfunction "1_1") (pintype "passive"))
      (node (ref "C84") (pin "1") (pinfunction "1_1") (pintype "passive"))
      (node (ref "C85") (pin "1") (pinfunction "1_1") (pintype "passive"))
      (node (ref "C86") (pin "2") (pinfunction "2_2") (pintype "passive"))
      (node (ref "C87") (pin "1") (pinfunction "1_1") (pintype "passive"))
      (node (ref "C88") (pin "1") (pinfunction "1_1") (pintype "passive"))
      (node (ref "C89") (pin "1") (pinfunction "1_1") (pintype "passive"))
      (node (ref "C90") (pin "1") (pinfunction "1_1") (pintype "passive"))
      (node (ref "D28") (pin "1") (pinfunction "1_1") (pintype "passive"))
      (node (ref "D53") (pin "1") (pinfunction "1_1") (pintype "passive"))
      (node (ref "D54") (pin "1") (pinfunction "1_1") (pintype "passive"))
      (node (ref "D55") (pin "1") (pinfunction "1_1") (pintype "passive"))
      (node (ref "D56") (pin "1") (pinfunction "1_1") (pintype "passive"))
      (node (ref "D57") (pin "1") (pinfunction "1_1") (pintype "passive"))
      (node (ref "D58") (pin "1") (pinfunction "1_1") (pintype "passive"))
      (node (ref "D59") (pin "1") (pinfunction "1_1") (pintype "passive"))
      (node (ref "D60") (pin "1") (pinfunction "1_1") (pintype "passive"))
      (node (ref "D61") (pin "1") (pinfunction "1_1") (pintype "passive"))
      (node (ref "D62") (pin "1") (pinfunction "1_1") (pintype "passive"))
      (node (ref "D63") (pin "1") (pinfunction "1_1") (pintype "passive"))
      (node (ref "D64") (pin "1") (pinfunction "1_1") (pintype "passive"))
      (node (ref "D65") (pin "1") (pinfunction "1_1") (pintype "passive"))
      (node (ref "D66") (pin "1") (pinfunction "1_1") (pintype "passive"))
      (node (ref "D67") (pin "1") (pinfunction "1_1") (pintype "passive"))
      (node (ref "D68") (pin "1") (pinfunction "1_1") (pintype "passive"))
      (node (ref "D69") (pin "1") (pinfunction "1_1") (pintype "passive"))
      (node (ref "D70") (pin "1") (pinfunction "1_1") (pintype "passive"))
      (node (ref "D71") (pin "1") (pinfunction "1_1") (pintype "passive"))
      (node (ref "D72") (pin "1") (pinfunction "1_1") (pintype "passive"))
      (node (ref "D73") (pin "1") (pinfunction "1_1") (pintype "passive"))
      (node (ref "D74") (pin "1") (pinfunction "1_1") (pintype "passive"))
      (node (ref "D75") (pin "1") (pinfunction "1_1") (pintype "passive"))
      (node (ref "D76") (pin "1") (pinfunction "1_1") (pintype "passive"))
      (node (ref "R114") (pin "1") (pinfunction "1_1") (pintype "passive"))
      (node (ref "R201") (pin "1") (pinfunction "1_1") (pintype "passive"))
      (node (ref "R203") (pin "2") (pinfunction "2_2") (pintype "passive"))
      (node (ref "R204") (pin "2") (pinfunction "2_2") (pintype "passive"))
      (node (ref "R205") (pin "2") (pinfunction "2_2") (pintype "passive"))
      (node (ref "U35") (pin "14") (pinfunction "GND_14") (pintype "passive"))
      (node (ref "U36") (pin "10") (pinfunction "S4B_10") (pintype "passive"))
      (node (ref "U36") (pin "11") (pinfunction "S3B_11") (pintype "passive"))
      (node (ref "U36") (pin "12") (pinfunction "S2B_12") (pintype "passive"))
      (node (ref "U36") (pin "13") (pinfunction "S1B_13") (pintype "passive"))
      (node (ref "U36") (pin "15") (pinfunction "GND_15") (pintype "input"))
      (node (ref "U36") (pin "7") (pinfunction "S4A_7") (pintype "passive"))
      (node (ref "U36") (pin "9") (pinfunction "DB_9") (pintype "passive"))
      (node (ref "U38") (pin "14") (pinfunction "GND_14") (pintype "passive"))
      (node (ref "U39") (pin "10") (pinfunction "S4B_10") (pintype "passive"))
      (node (ref "U39") (pin "11") (pinfunction "S3B_11") (pintype "passive"))
      (node (ref "U39") (pin "12") (pinfunction "S2B_12") (pintype "passive"))
      (node (ref "U39") (pin "13") (pinfunction "S1B_13") (pintype "passive"))
      (node (ref "U39") (pin "15") (pinfunction "GND_15") (pintype "input"))
      (node (ref "U39") (pin "9") (pinfunction "DB_9") (pintype "passive"))
      (node (ref "U40") (pin "14") (pinfunction "GND_14") (pintype "passive"))
      (node (ref "U44") (pin "3") (pinfunction "3_3") (pintype "passive"))
    )
    (net (code "44") (name "Net-(D28-Pad2)") (class "Default")
      (node (ref "D28") (pin "2") (pinfunction "2_2") (pintype "passive"))
      (node (ref "R111") (pin "2") (pinfunction "2_2") (pintype "passive"))
      (node (ref "R112") (pin "2") (pinfunction "2_2") (pintype "passive"))
    )
    (net (code "45") (name "Net-(R113-Pad1)") (class "Default")
      (node (ref "R113") (pin "1") (pinfunction "1_1") (pintype "passive"))
      (node (ref "U37") (pin "5") (pinfunction "5_5") (pintype "passive"))
    )
    (net (code "46") (name "Net-(R113-Pad2)") (class "Default")
      (node (ref "R113") (pin "2") (pinfunction "2_2") (pintype "passive"))
      (node (ref "R144") (pin "1") (pinfunction "1_1") (pintype "passive"))
      (node (ref "TP51") (pin "1") (pinfunction "1_1") (pintype "passive"))
      (node (ref "U37") (pin "1") (pinfunction "1_1") (pintype "passive"))
    )
    (net (code "47") (name "Net-(R143-Pad1)") (class "Default")
      (node (ref "R143") (pin "1") (pinfunction "1_1") (pintype "passive"))
      (node (ref "TP50") (pin "1") (pinfunction "1_1") (pintype "passive"))
      (node (ref "U37") (pin "7") (pinfunction "7_7") (pintype "passive"))
    )
    (net (code "48") (name "Net-(R144-Pad2)") (class "Default")
      (node (ref "R144") (pin "2") (pinfunction "2_2") (pintype "passive"))
      (node (ref "U37") (pin "2") (pinfunction "2_2") (pintype "passive"))
    )
    (net (code "49") (name "Net-(R199-Pad1)") (class "Default")
      (node (ref "R199") (pin "1") (pinfunction "1_1") (pintype "passive"))
      (node (ref "R201") (pin "2") (pinfunction "2_2") (pintype "passive"))
      (node (ref "TP57") (pin "1") (pinfunction "1_1") (pintype "passive"))
      (node (ref "U37") (pin "3") (pinfunction "3_3") (pintype "passive"))
    )
    (net (code "50") (name "Net-(R199-Pad2)") (class "Default")
      (node (ref "R199") (pin "2") (pinfunction "2_2") (pintype "passive"))
      (node (ref "R200") (pin "1") (pinfunction "1_1") (pintype "passive"))
      (node (ref "TP58") (pin "1") (pinfunction "1_1") (pintype "passive"))
      (node (ref "U44") (pin "7") (pinfunction "7_7") (pintype "passive"))
    )
    (net (code "51") (name "Net-(R200-Pad2)") (class "Default")
      (node (ref "R200") (pin "2") (pinfunction "2_2") (pintype "passive"))
      (node (ref "U44") (pin "6") (pinfunction "6_6") (pintype "passive"))
    )
    (net (code "52") (name "Net-(R202-Pad1)") (class "Default")
      (node (ref "R202") (pin "1") (pinfunction "1_1") (pintype "passive"))
      (node (ref "U44") (pin "1") (pinfunction "1_1") (pintype "passive"))
    )
    (net (code "53") (name "Net-(R202-Pad2)") (class "Default")
      (node (ref "R202") (pin "2") (pinfunction "2_2") (pintype "passive"))
      (node (ref "U44") (pin "2") (pinfunction "2_2") (pintype "passive"))
    )
    (net (code "54") (name "Net-(U35-S1)") (class "Default")
      (node (ref "R165") (pin "2") (pinfunction "2_2") (pintype "passive"))
      (node (ref "U35") (pin "4") (pinfunction "S1_4") (pintype "passive"))
    )
    (net (code "55") (name "Net-(U35-S2)") (class "Default")
      (node (ref "R166") (pin "2") (pinfunction "2_2") (pintype "passive"))
      (node (ref "U35") (pin "5") (pinfunction "S2_5") (pintype "passive"))
    )
    (net (code "56") (name "Net-(U35-S3)") (class "Default")
      (node (ref "R167") (pin "2") (pinfunction "2_2") (pintype "passive"))
      (node (ref "U35") (pin "6") (pinfunction "S3_6") (pintype "passive"))
    )
    (net (code "57") (name "Net-(U35-S4)") (class "Default")
      (node (ref "R168") (pin "2") (pinfunction "2_2") (pintype "passive"))
      (node (ref "U35") (pin "7") (pinfunction "S4_7") (pintype "passive"))
    )
    (net (code "58") (name "Net-(U35-S5)") (class "Default")
      (node (ref "R169") (pin "2") (pinfunction "2_2") (pintype "passive"))
      (node (ref "U35") (pin "12") (pinfunction "S5_12") (pintype "passive"))
    )
    (net (code "59") (name "Net-(U35-S6)") (class "Default")
      (node (ref "R170") (pin "2") (pinfunction "2_2") (pintype "passive"))
      (node (ref "U35") (pin "11") (pinfunction "S6_11") (pintype "passive"))
    )
    (net (code "60") (name "Net-(U35-S7)") (class "Default")
      (node (ref "R171") (pin "2") (pinfunction "2_2") (pintype "passive"))
      (node (ref "U35") (pin "10") (pinfunction "S7_10") (pintype "passive"))
    )
    (net (code "61") (name "Net-(U35-S8)") (class "Default")
      (node (ref "R172") (pin "2") (pinfunction "2_2") (pintype "passive"))
      (node (ref "U35") (pin "9") (pinfunction "S8_9") (pintype "passive"))
    )
    (net (code "62") (name "Net-(U36-DA)") (class "Default")
      (node (ref "TP37") (pin "1") (pinfunction "1_1") (pintype "passive"))
      (node (ref "U36") (pin "8") (pinfunction "DA_8") (pintype "passive"))
      (node (ref "U44") (pin "5") (pinfunction "5_5") (pintype "passive"))
    )
    (net (code "63") (name "Net-(U38-S1)") (class "Default")
      (node (ref "R173") (pin "2") (pinfunction "2_2") (pintype "passive"))
      (node (ref "U38") (pin "4") (pinfunction "S1_4") (pintype "passive"))
    )
    (net (code "64") (name "Net-(U38-S2)") (class "Default")
      (node (ref "R174") (pin "2") (pinfunction "2_2") (pintype "passive"))
      (node (ref "U38") (pin "5") (pinfunction "S2_5") (pintype "passive"))
    )
    (net (code "65") (name "Net-(U38-S3)") (class "Default")
      (node (ref "R175") (pin "2") (pinfunction "2_2") (pintype "passive"))
      (node (ref "U38") (pin "6") (pinfunction "S3_6") (pintype "passive"))
    )
    (net (code "66") (name "Net-(U38-S4)") (class "Default")
      (node (ref "R176") (pin "2") (pinfunction "2_2") (pintype "passive"))
      (node (ref "U38") (pin "7") (pinfunction "S4_7") (pintype "passive"))
    )
    (net (code "67") (name "Net-(U38-S5)") (class "Default")
      (node (ref "R177") (pin "2") (pinfunction "2_2") (pintype "passive"))
      (node (ref "U38") (pin "12") (pinfunction "S5_12") (pintype "passive"))
    )
    (net (code "68") (name "Net-(U38-S6)") (class "Default")
      (node (ref "R178") (pin "2") (pinfunction "2_2") (pintype "passive"))
      (node (ref "U38") (pin "11") (pinfunction "S6_11") (pintype "passive"))
    )
    (net (code "69") (name "Net-(U38-S7)") (class "Default")
      (node (ref "R179") (pin "2") (pinfunction "2_2") (pintype "passive"))
      (node (ref "U38") (pin "10") (pinfunction "S7_10") (pintype "passive"))
    )
    (net (code "70") (name "Net-(U38-S8)") (class "Default")
      (node (ref "R180") (pin "2") (pinfunction "2_2") (pintype "passive"))
      (node (ref "U38") (pin "9") (pinfunction "S8_9") (pintype "passive"))
    )
    (net (code "71") (name "Net-(U39-DA)") (class "Default")
      (node (ref "R114") (pin "2") (pinfunction "2_2") (pintype "passive"))
      (node (ref "TP39") (pin "1") (pinfunction "1_1") (pintype "passive"))
      (node (ref "U37") (pin "6") (pinfunction "6_6") (pintype "passive"))
      (node (ref "U39") (pin "8") (pinfunction "DA_8") (pintype "passive"))
    )
    (net (code "72") (name "Net-(U39-S1A)") (class "Default")
      (node (ref "D28") (pin "3") (pinfunction "3_3") (pintype "passive"))
      (node (ref "R110") (pin "2") (pinfunction "2_2") (pintype "passive"))
      (node (ref "R115") (pin "1") (pinfunction "1_1") (pintype "passive"))
      (node (ref "R116") (pin "1") (pinfunction "1_1") (pintype "passive"))
      (node (ref "R117") (pin "1") (pinfunction "1_1") (pintype "passive"))
      (node (ref "R143") (pin "2") (pinfunction "2_2") (pintype "passive"))
      (node (ref "TP36") (pin "1") (pinfunction "1_1") (pintype "passive"))
      (node (ref "U39") (pin "4") (pinfunction "S1A_4") (pintype "passive"))
    )
    (net (code "73") (name "Net-(U39-S2A)") (class "Default")
      (node (ref "R115") (pin "2") (pinfunction "2_2") (pintype "passive"))
      (node (ref "U39") (pin "5") (pinfunction "S2A_5") (pintype "passive"))
    )
    (net (code "74") (name "Net-(U39-S3A)") (class "Default")
      (node (ref "R116") (pin "2") (pinfunction "2_2") (pintype "passive"))
      (node (ref "U39") (pin "6") (pinfunction "S3A_6") (pintype "passive"))
    )
    (net (code "75") (name "Net-(U39-S4A)") (class "Default")
      (node (ref "R117") (pin "2") (pinfunction "2_2") (pintype "passive"))
      (node (ref "U39") (pin "7") (pinfunction "S4A_7") (pintype "passive"))
    )
    (net (code "76") (name "Net-(U40-S1)") (class "Default")
      (node (ref "R181") (pin "2") (pinfunction "2_2") (pintype "passive"))
      (node (ref "U40") (pin "4") (pinfunction "S1_4") (pintype "passive"))
    )
    (net (code "77") (name "Net-(U40-S2)") (class "Default")
      (node (ref "R182") (pin "2") (pinfunction "2_2") (pintype "passive"))
      (node (ref "U40") (pin "5") (pinfunction "S2_5") (pintype "passive"))
    )
    (net (code "78") (name "Net-(U40-S3)") (class "Default")
      (node (ref "R183") (pin "2") (pinfunction "2_2") (pintype "passive"))
      (node (ref "U40") (pin "6") (pinfunction "S3_6") (pintype "passive"))
    )
    (net (code "79") (name "Net-(U40-S4)") (class "Default")
      (node (ref "R184") (pin "2") (pinfunction "2_2") (pintype "passive"))
      (node (ref "U40") (pin "7") (pinfunction "S4_7") (pintype "passive"))
    )
    (net (code "80") (name "Net-(U40-S5)") (class "Default")
      (node (ref "R185") (pin "2") (pinfunction "2_2") (pintype "passive"))
      (node (ref "U40") (pin "12") (pinfunction "S5_12") (pintype "passive"))
    )
    (net (code "81") (name "Net-(U40-S6)") (class "Default")
      (node (ref "R186") (pin "2") (pinfunction "2_2") (pintype "passive"))
      (node (ref "U40") (pin "11") (pinfunction "S6_11") (pintype "passive"))
    )
    (net (code "82") (name "Net-(U40-S7)") (class "Default")
      (node (ref "R187") (pin "2") (pinfunction "2_2") (pintype "passive"))
      (node (ref "U40") (pin "10") (pinfunction "S7_10") (pintype "passive"))
    )
    (net (code "83") (name "Net-(U40-S8)") (class "Default")
      (node (ref "R188") (pin "2") (pinfunction "2_2") (pintype "passive"))
      (node (ref "U40") (pin "9") (pinfunction "S8_9") (pintype "passive"))
    )
  )
)
